# CPLD_Adapter.net
KiCad netlist of a schematic drawn in EAGLE
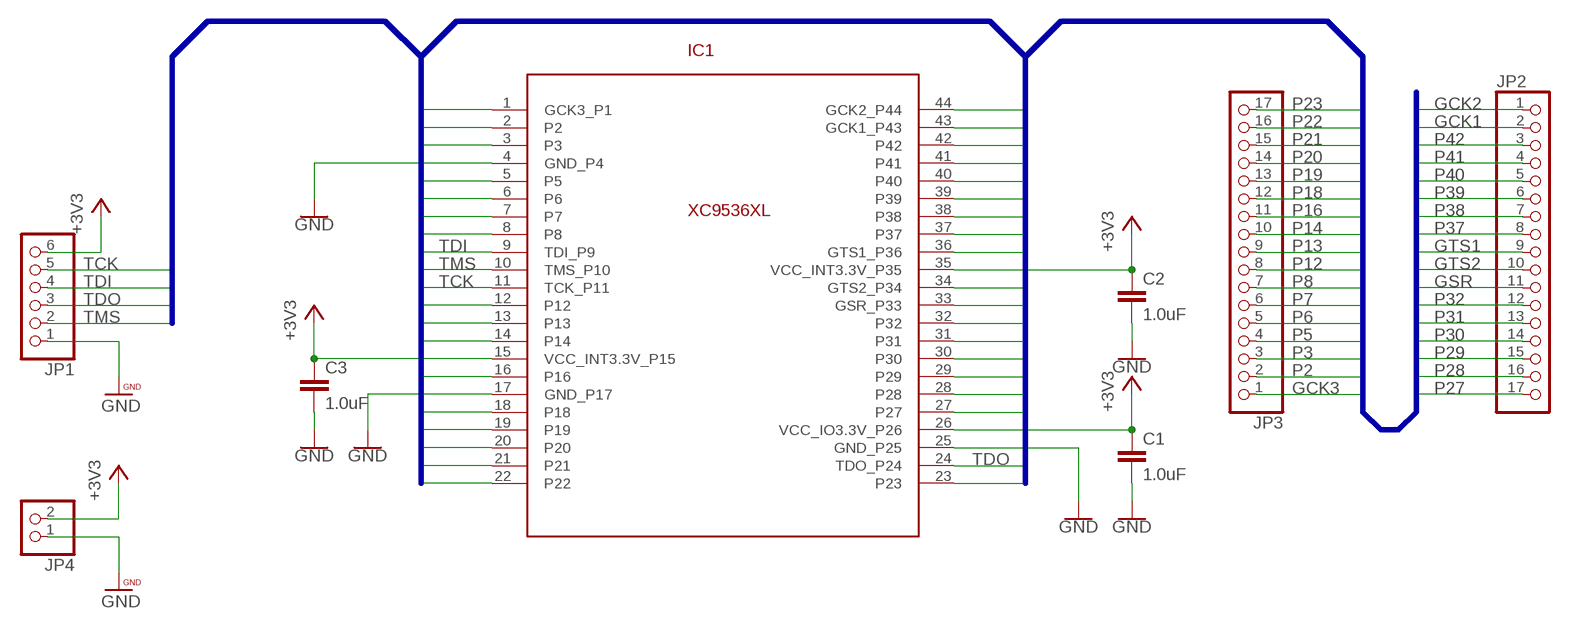
[diagram p0: schematic, sheet 1]

(export (version "E")
  (design (tool "Eeschema 10.0.6"))
  (components
    (comp (ref "C1")
      (value "1.0uF")
      (footprint "eagle-import:0603")
      (libsource (lib "eagle-import") (part "1.0UF-0603-16V-10%"))
    )
    (comp (ref "C2")
      (value "1.0uF")
      (footprint "eagle-import:0603")
      (libsource (lib "eagle-import") (part "1.0UF-0603-16V-10%"))
    )
    (comp (ref "C3")
      (value "1.0uF")
      (footprint "eagle-import:0603")
      (libsource (lib "eagle-import") (part "1.0UF-0603-16V-10%"))
    )
    (comp (ref "IC1")
      (value "XC9536XL")
      (footprint "eagle-import:QFP80P1200X1200X105-44")
      (libsource (lib "eagle-import") (part "XC9536XL"))
    )
    (comp (ref "JP1")
      (value "PINHD-1X6")
      (footprint "eagle-import:1X06")
      (libsource (lib "eagle-import") (part "PINHD-1X6"))
    )
    (comp (ref "JP2")
      (value "PINHD-1X17")
      (footprint "eagle-import:1X17")
      (libsource (lib "eagle-import") (part "PINHD-1X17"))
    )
    (comp (ref "JP3")
      (value "PINHD-1X17")
      (footprint "eagle-import:1X17")
      (libsource (lib "eagle-import") (part "PINHD-1X17"))
    )
    (comp (ref "JP4")
      (value "PINHD-1X2")
      (footprint "eagle-import:1X02")
      (libsource (lib "eagle-import") (part "PINHD-1X2"))
    )
  )
  (nets
    (net (code "1") (name "+3V3") (class "Default")
      (node (ref "C1") (pin "1") (pinfunction "1_1") (pintype "passive"))
      (node (ref "C2") (pin "1") (pinfunction "1_1") (pintype "passive"))
      (node (ref "C3") (pin "1") (pinfunction "1_1") (pintype "passive"))
      (node (ref "IC1") (pin "15") (pinfunction "VCC_INT3.3V_P15_15") (pintype "bidirectional"))
      (node (ref "IC1") (pin "26") (pinfunction "VCC_IO3.3V_P26_26") (pintype "bidirectional"))
      (node (ref "IC1") (pin "35") (pinfunction "VCC_INT3.3V_P35_35") (pintype "bidirectional"))
      (node (ref "JP1") (pin "6") (pinfunction "6_6") (pintype "passive"))
      (node (ref "JP4") (pin "2") (pinfunction "2_2") (pintype "passive"))
    )
    (net (code "2") (name "/GCK1") (class "Default")
      (node (ref "IC1") (pin "43") (pinfunction "GCK1_P43_43") (pintype "bidirectional"))
      (node (ref "JP2") (pin "2") (pinfunction "2_2") (pintype "passive"))
    )
    (net (code "3") (name "/GCK2") (class "Default")
      (node (ref "IC1") (pin "44") (pinfunction "GCK2_P44_44") (pintype "bidirectional"))
      (node (ref "JP2") (pin "1") (pinfunction "1_1") (pintype "passive"))
    )
    (net (code "4") (name "/GCK3") (class "Default")
      (node (ref "IC1") (pin "1") (pinfunction "GCK3_P1_1") (pintype "bidirectional"))
      (node (ref "JP3") (pin "1") (pinfunction "1_1") (pintype "passive"))
    )
    (net (code "5") (name "/GSR") (class "Default")
      (node (ref "IC1") (pin "33") (pinfunction "GSR_P33_33") (pintype "bidirectional"))
      (node (ref "JP2") (pin "11") (pinfunction "11_11") (pintype "passive"))
    )
    (net (code "6") (name "/GTS1") (class "Default")
      (node (ref "IC1") (pin "36") (pinfunction "GTS1_P36_36") (pintype "bidirectional"))
      (node (ref "JP2") (pin "9") (pinfunction "9_9") (pintype "passive"))
    )
    (net (code "7") (name "/GTS2") (class "Default")
      (node (ref "IC1") (pin "34") (pinfunction "GTS2_P34_34") (pintype "bidirectional"))
      (node (ref "JP2") (pin "10") (pinfunction "10_10") (pintype "passive"))
    )
    (net (code "8") (name "/P2") (class "Default")
      (node (ref "IC1") (pin "2") (pinfunction "P2_2") (pintype "bidirectional"))
      (node (ref "JP3") (pin "2") (pinfunction "2_2") (pintype "passive"))
    )
    (net (code "9") (name "/P3") (class "Default")
      (node (ref "IC1") (pin "3") (pinfunction "P3_3") (pintype "bidirectional"))
      (node (ref "JP3") (pin "3") (pinfunction "3_3") (pintype "passive"))
    )
    (net (code "10") (name "/P5") (class "Default")
      (node (ref "IC1") (pin "5") (pinfunction "P5_5") (pintype "bidirectional"))
      (node (ref "JP3") (pin "4") (pinfunction "4_4") (pintype "passive"))
    )
    (net (code "11") (name "/P6") (class "Default")
      (node (ref "IC1") (pin "6") (pinfunction "P6_6") (pintype "bidirectional"))
      (node (ref "JP3") (pin "5") (pinfunction "5_5") (pintype "passive"))
    )
    (net (code "12") (name "/P7") (class "Default")
      (node (ref "IC1") (pin "7") (pinfunction "P7_7") (pintype "bidirectional"))
      (node (ref "JP3") (pin "6") (pinfunction "6_6") (pintype "passive"))
    )
    (net (code "13") (name "/P8") (class "Default")
      (node (ref "IC1") (pin "8") (pinfunction "P8_8") (pintype "bidirectional"))
      (node (ref "JP3") (pin "7") (pinfunction "7_7") (pintype "passive"))
    )
    (net (code "14") (name "/P12") (class "Default")
      (node (ref "IC1") (pin "12") (pinfunction "P12_12") (pintype "bidirectional"))
      (node (ref "JP3") (pin "8") (pinfunction "8_8") (pintype "passive"))
    )
    (net (code "15") (name "/P13") (class "Default")
      (node (ref "IC1") (pin "13") (pinfunction "P13_13") (pintype "bidirectional"))
      (node (ref "JP3") (pin "9") (pinfunction "9_9") (pintype "passive"))
    )
    (net (code "16") (name "/P14") (class "Default")
      (node (ref "IC1") (pin "14") (pinfunction "P14_14") (pintype "bidirectional"))
      (node (ref "JP3") (pin "10") (pinfunction "10_10") (pintype "passive"))
    )
    (net (code "17") (name "/P16") (class "Default")
      (node (ref "IC1") (pin "16") (pinfunction "P16_16") (pintype "bidirectional"))
      (node (ref "JP3") (pin "11") (pinfunction "11_11") (pintype "passive"))
    )
    (net (code "18") (name "/P18") (class "Default")
      (node (ref "IC1") (pin "18") (pinfunction "P18_18") (pintype "bidirectional"))
      (node (ref "JP3") (pin "12") (pinfunction "12_12") (pintype "passive"))
    )
    (net (code "19") (name "/P19") (class "Default")
      (node (ref "IC1") (pin "19") (pinfunction "P19_19") (pintype "bidirectional"))
      (node (ref "JP3") (pin "13") (pinfunction "13_13") (pintype "passive"))
    )
    (net (code "20") (name "/P20") (class "Default")
      (node (ref "IC1") (pin "20") (pinfunction "P20_20") (pintype "bidirectional"))
      (node (ref "JP3") (pin "14") (pinfunction "14_14") (pintype "passive"))
    )
    (net (code "21") (name "/P21") (class "Default")
      (node (ref "IC1") (pin "21") (pinfunction "P21_21") (pintype "bidirectional"))
      (node (ref "JP3") (pin "15") (pinfunction "15_15") (pintype "passive"))
    )
    (net (code "22") (name "/P22") (class "Default")
      (node (ref "IC1") (pin "22") (pinfunction "P22_22") (pintype "bidirectional"))
      (node (ref "JP3") (pin "16") (pinfunction "16_16") (pintype "passive"))
    )
    (net (code "23") (name "/P23") (class "Default")
      (node (ref "IC1") (pin "23") (pinfunction "P23_23") (pintype "bidirectional"))
      (node (ref "JP3") (pin "17") (pinfunction "17_17") (pintype "passive"))
    )
    (net (code "24") (name "/P27") (class "Default")
      (node (ref "IC1") (pin "27") (pinfunction "P27_27") (pintype "bidirectional"))
      (node (ref "JP2") (pin "17") (pinfunction "17_17") (pintype "passive"))
    )
    (net (code "25") (name "/P28") (class "Default")
      (node (ref "IC1") (pin "28") (pinfunction "P28_28") (pintype "bidirectional"))
      (node (ref "JP2") (pin "16") (pinfunction "16_16") (pintype "passive"))
    )
    (net (code "26") (name "/P29") (class "Default")
      (node (ref "IC1") (pin "29") (pinfunction "P29_29") (pintype "bidirectional"))
      (node (ref "JP2") (pin "15") (pinfunction "15_15") (pintype "passive"))
    )
    (net (code "27") (name "/P30") (class "Default")
      (node (ref "IC1") (pin "30") (pinfunction "P30_30") (pintype "bidirectional"))
      (node (ref "JP2") (pin "14") (pinfunction "14_14") (pintype "passive"))
    )
    (net (code "28") (name "/P31") (class "Default")
      (node (ref "IC1") (pin "31") (pinfunction "P31_31") (pintype "bidirectional"))
      (node (ref "JP2") (pin "13") (pinfunction "13_13") (pintype "passive"))
    )
    (net (code "29") (name "/P32") (class "Default")
      (node (ref "IC1") (pin "32") (pinfunction "P32_32") (pintype "bidirectional"))
      (node (ref "JP2") (pin "12") (pinfunction "12_12") (pintype "passive"))
    )
    (net (code "30") (name "/P37") (class "Default")
      (node (ref "IC1") (pin "37") (pinfunction "P37_37") (pintype "bidirectional"))
      (node (ref "JP2") (pin "8") (pinfunction "8_8") (pintype "passive"))
    )
    (net (code "31") (name "/P38") (class "Default")
      (node (ref "IC1") (pin "38") (pinfunction "P38_38") (pintype "bidirectional"))
      (node (ref "JP2") (pin "7") (pinfunction "7_7") (pintype "passive"))
    )
    (net (code "32") (name "/P39") (class "Default")
      (node (ref "IC1") (pin "39") (pinfunction "P39_39") (pintype "bidirectional"))
      (node (ref "JP2") (pin "6") (pinfunction "6_6") (pintype "passive"))
    )
    (net (code "33") (name "/P40") (class "Default")
      (node (ref "IC1") (pin "40") (pinfunction "P40_40") (pintype "bidirectional"))
      (node (ref "JP2") (pin "5") (pinfunction "5_5") (pintype "passive"))
    )
    (net (code "34") (name "/P41") (class "Default")
      (node (ref "IC1") (pin "41") (pinfunction "P41_41") (pintype "bidirectional"))
      (node (ref "JP2") (pin "4") (pinfunction "4_4") (pintype "passive"))
    )
    (net (code "35") (name "/P42") (class "Default")
      (node (ref "IC1") (pin "42") (pinfunction "P42_42") (pintype "bidirectional"))
      (node (ref "JP2") (pin "3") (pinfunction "3_3") (pintype "passive"))
    )
    (net (code "36") (name "/TCK") (class "Default")
      (node (ref "IC1") (pin "11") (pinfunction "TCK_P11_11") (pintype "bidirectional"))
      (node (ref "JP1") (pin "5") (pinfunction "5_5") (pintype "passive"))
    )
    (net (code "37") (name "/TDI") (class "Default")
      (node (ref "IC1") (pin "9") (pinfunction "TDI_P9_9") (pintype "bidirectional"))
      (node (ref "JP1") (pin "4") (pinfunction "4_4") (pintype "passive"))
    )
    (net (code "38") (name "/TDO") (class "Default")
      (node (ref "IC1") (pin "24") (pinfunction "TDO_P24_24") (pintype "bidirectional"))
      (node (ref "JP1") (pin "3") (pinfunction "3_3") (pintype "passive"))
    )
    (net (code "39") (name "/TMS") (class "Default")
      (node (ref "IC1") (pin "10") (pinfunction "TMS_P10_10") (pintype "bidirectional"))
      (node (ref "JP1") (pin "2") (pinfunction "2_2") (pintype "passive"))
    )
    (net (code "40") (name "GND") (class "Default")
      (node (ref "C1") (pin "2") (pinfunction "2_2") (pintype "passive"))
      (node (ref "C2") (pin "2") (pinfunction "2_2") (pintype "passive"))
      (node (ref "C3") (pin "2") (pinfunction "2_2") (pintype "passive"))
      (node (ref "IC1") (pin "17") (pinfunction "GND_P17_17") (pintype "bidirectional"))
      (node (ref "IC1") (pin "25") (pinfunction "GND_P25_25") (pintype "bidirectional"))
      (node (ref "IC1") (pin "4") (pinfunction "GND_P4_4") (pintype "bidirectional"))
      (node (ref "JP1") (pin "1") (pinfunction "1_1") (pintype "passive"))
      (node (ref "JP4") (pin "1") (pinfunction "1_1") (pintype "passive"))
    )
  )
)
